# ECG_V4.net
KiCad netlist of a schematic drawn in EAGLE
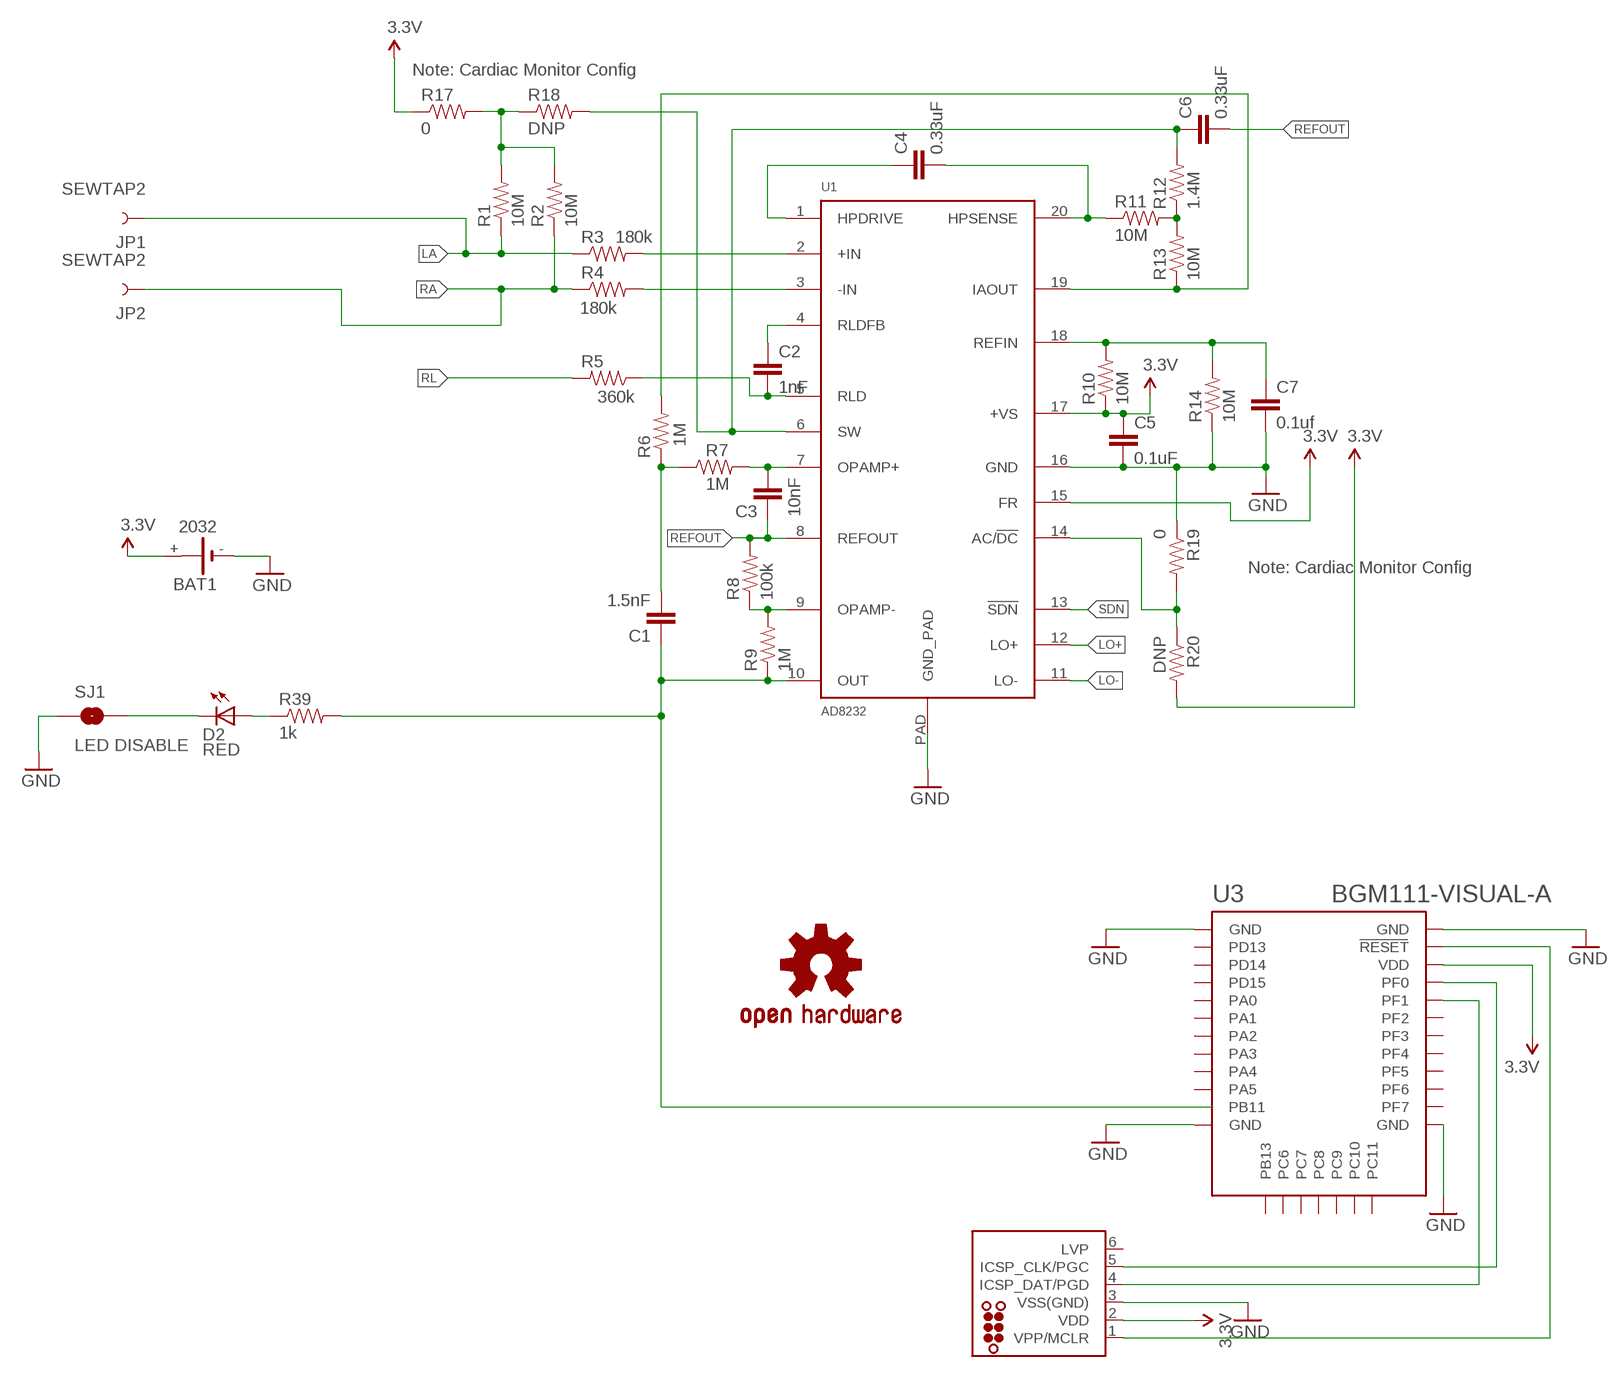
[diagram p0: schematic, sheet 1]

(export (version "E")
  (design (tool "Eeschema 10.0.6"))
  (components
    (comp (ref "BAT1")
      (value "2032")
      (footprint "eagle-import:KZH20SMD")
      (libsource (lib "eagle-import") (part "2032"))
    )
    (comp (ref "C1")
      (value "1.5nF")
      (footprint "eagle-import:0603-CAP")
      (libsource (lib "eagle-import") (part "CAP0603-CAP"))
    )
    (comp (ref "C2")
      (value "1nF")
      (footprint "eagle-import:0603-CAP")
      (libsource (lib "eagle-import") (part "CAP0603-CAP"))
    )
    (comp (ref "C3")
      (value "10nF")
      (footprint "eagle-import:0603-CAP")
      (libsource (lib "eagle-import") (part "CAP0603-CAP"))
    )
    (comp (ref "C4")
      (value "0.33uF")
      (footprint "eagle-import:0805")
      (libsource (lib "eagle-import") (part "CAP0805"))
    )
    (comp (ref "C5")
      (value "0.1uF")
      (footprint "eagle-import:0603-CAP")
      (libsource (lib "eagle-import") (part "CAP0603-CAP"))
    )
    (comp (ref "C6")
      (value "0.33uF")
      (footprint "eagle-import:0805")
      (libsource (lib "eagle-import") (part "CAP0805"))
    )
    (comp (ref "C7")
      (value "0.1uf")
      (footprint "eagle-import:0603-CAP")
      (libsource (lib "eagle-import") (part "CAP0603-CAP"))
    )
    (comp (ref "D2")
      (value "RED")
      (footprint "eagle-import:LED-0603")
      (libsource (lib "eagle-import") (part "LED-RED0603"))
    )
    (comp (ref "J2")
      (value "TC2030-MCP-NL")
      (footprint "eagle-import:TC2030-MCP-NL")
      (libsource (lib "eagle-import") (part "TC2030-MCP-NL"))
    )
    (comp (ref "JP1")
      (value "SEWTAP2")
      (footprint "eagle-import:PETAL-LONG-2")
      (libsource (lib "eagle-import") (part "SEWTAP2"))
    )
    (comp (ref "JP2")
      (value "SEWTAP2")
      (footprint "eagle-import:PETAL-LONG-2")
      (libsource (lib "eagle-import") (part "SEWTAP2"))
    )
    (comp (ref "LOGO1")
      (value "OSHW-LOGOS")
      (footprint "eagle-import:OSHW-LOGO-S")
      (libsource (lib "eagle-import") (part "OSHW-LOGOS"))
    )
    (comp (ref "R1")
      (value "10M")
      (footprint "eagle-import:0603-RES")
      (libsource (lib "eagle-import") (part "RESISTOR0603-RES"))
    )
    (comp (ref "R2")
      (value "10M")
      (footprint "eagle-import:0603-RES")
      (libsource (lib "eagle-import") (part "RESISTOR0603-RES"))
    )
    (comp (ref "R3")
      (value "180k")
      (footprint "eagle-import:0603-RES")
      (libsource (lib "eagle-import") (part "RESISTOR0603-RES"))
    )
    (comp (ref "R4")
      (value "180k")
      (footprint "eagle-import:0603-RES")
      (libsource (lib "eagle-import") (part "RESISTOR0603-RES"))
    )
    (comp (ref "R5")
      (value "360k")
      (footprint "eagle-import:0603-RES")
      (libsource (lib "eagle-import") (part "RESISTOR0603-RES"))
    )
    (comp (ref "R6")
      (value "1M")
      (footprint "eagle-import:0603-RES")
      (libsource (lib "eagle-import") (part "RESISTOR0603-RES"))
    )
    (comp (ref "R7")
      (value "1M")
      (footprint "eagle-import:0603-RES")
      (libsource (lib "eagle-import") (part "RESISTOR0603-RES"))
    )
    (comp (ref "R8")
      (value "100k")
      (footprint "eagle-import:0603-RES")
      (libsource (lib "eagle-import") (part "RESISTOR0603-RES"))
    )
    (comp (ref "R9")
      (value "1M")
      (footprint "eagle-import:0603-RES")
      (libsource (lib "eagle-import") (part "RESISTOR0603-RES"))
    )
    (comp (ref "R10")
      (value "10M")
      (footprint "eagle-import:0603-RES")
      (libsource (lib "eagle-import") (part "RESISTOR0603-RES"))
    )
    (comp (ref "R11")
      (value "10M")
      (footprint "eagle-import:0603-RES")
      (libsource (lib "eagle-import") (part "RESISTOR0603-RES"))
    )
    (comp (ref "R12")
      (value "1.4M")
      (footprint "eagle-import:0603-RES")
      (libsource (lib "eagle-import") (part "RESISTOR0603-RES"))
    )
    (comp (ref "R13")
      (value "10M")
      (footprint "eagle-import:0603-RES")
      (libsource (lib "eagle-import") (part "RESISTOR0603-RES"))
    )
    (comp (ref "R14")
      (value "10M")
      (footprint "eagle-import:0603-RES")
      (libsource (lib "eagle-import") (part "RESISTOR0603-RES"))
    )
    (comp (ref "R17")
      (value "0")
      (footprint "eagle-import:0603")
      (libsource (lib "eagle-import") (part "0OHM1/10W5%(0603)"))
    )
    (comp (ref "R18")
      (value "DNP")
      (footprint "eagle-import:0603")
      (libsource (lib "eagle-import") (part "0OHM1/10W5%(0603)"))
    )
    (comp (ref "R19")
      (value "0")
      (footprint "eagle-import:0603")
      (libsource (lib "eagle-import") (part "0OHM1/10W5%(0603)"))
    )
    (comp (ref "R20")
      (value "DNP")
      (footprint "eagle-import:0603")
      (libsource (lib "eagle-import") (part "0OHM1/10W5%(0603)"))
    )
    (comp (ref "R39")
      (value "1k")
      (footprint "eagle-import:0603-RES")
      (libsource (lib "eagle-import") (part "1K-1%"))
    )
    (comp (ref "SJ1")
      (value "LED DISABLE")
      (footprint "eagle-import:SJ_2S-TRACE")
      (libsource (lib "eagle-import") (part "SOLDERJUMPERTRACE"))
    )
    (comp (ref "U1")
      (value "AD8232")
      (footprint "eagle-import:LFCSP_20")
      (libsource (lib "eagle-import") (part "AD8232"))
    )
    (comp (ref "U3")
      (value "BGM111-VISUAL-A")
      (footprint "eagle-import:BGM111-A")
      (libsource (lib "eagle-import") (part "BGM111-VISUAL-A"))
    )
  )
  (nets
    (net (code "1") (name "3.3V") (class "Default")
      (node (ref "BAT1") (pin "+") (pinfunction "+_+") (pintype "passive"))
      (node (ref "C5") (pin "1") (pinfunction "1_1") (pintype "passive"))
      (node (ref "J2") (pin "2") (pinfunction "VDD_2") (pintype "power_in"))
      (node (ref "R10") (pin "1") (pinfunction "1_1") (pintype "passive"))
      (node (ref "R17") (pin "1") (pinfunction "1_1") (pintype "passive"))
      (node (ref "R20") (pin "2") (pinfunction "2_2") (pintype "passive"))
      (node (ref "U1") (pin "15") (pinfunction "FR_15") (pintype "bidirectional"))
      (node (ref "U1") (pin "17") (pinfunction "+VS_17") (pintype "bidirectional"))
      (node (ref "U3") (pin "VDD") (pinfunction "VDD_VDD") (pintype "power_in"))
    )
    (net (code "2") (name "GND") (class "Default")
      (node (ref "BAT1") (pin "-") (pinfunction "-_-") (pintype "passive"))
      (node (ref "C5") (pin "2") (pinfunction "2_2") (pintype "passive"))
      (node (ref "C7") (pin "2") (pinfunction "2_2") (pintype "passive"))
      (node (ref "J2") (pin "3") (pinfunction "VSS(GND)_3") (pintype "power_in"))
      (node (ref "R14") (pin "1") (pinfunction "1_1") (pintype "passive"))
      (node (ref "R19") (pin "1") (pinfunction "1_1") (pintype "passive"))
      (node (ref "SJ1") (pin "1") (pinfunction "1_1") (pintype "passive"))
      (node (ref "U1") (pin "16") (pinfunction "GND_16") (pintype "bidirectional"))
      (node (ref "U1") (pin "PAD") (pinfunction "GND_PAD_PAD") (pintype "bidirectional"))
      (node (ref "U3") (pin "GND") (pinfunction "GND_GND") (pintype "power_in"))
      (node (ref "U3") (pin "GND@2") (pinfunction "GND_GND@2") (pintype "power_in"))
      (node (ref "U3") (pin "GND@3") (pinfunction "GND_GND@3") (pintype "power_in"))
      (node (ref "U3") (pin "GND@4") (pinfunction "GND_GND@4") (pintype "power_in"))
    )
    (net (code "3") (name "LA") (class "Default")
      (node (ref "JP1") (pin "1") (pinfunction "1_1") (pintype "bidirectional"))
      (node (ref "R1") (pin "1") (pinfunction "1_1") (pintype "passive"))
      (node (ref "R3") (pin "1") (pinfunction "1_1") (pintype "passive"))
    )
    (net (code "4") (name "LO+") (class "Default")
      (node (ref "U1") (pin "12") (pinfunction "LO+_12") (pintype "bidirectional"))
    )
    (net (code "5") (name "LO-") (class "Default")
      (node (ref "U1") (pin "11") (pinfunction "LO-_11") (pintype "bidirectional"))
    )
    (net (code "6") (name "Net-(C1-Pad2)") (class "Default")
      (node (ref "C1") (pin "2") (pinfunction "2_2") (pintype "passive"))
      (node (ref "R6") (pin "1") (pinfunction "1_1") (pintype "passive"))
      (node (ref "R7") (pin "1") (pinfunction "1_1") (pintype "passive"))
    )
    (net (code "7") (name "Net-(D2-PadA)") (class "Default")
      (node (ref "D2") (pin "A") (pinfunction "A_A") (pintype "passive"))
      (node (ref "R39") (pin "1") (pinfunction "1_1") (pintype "passive"))
    )
    (net (code "8") (name "Net-(D2-PadC)") (class "Default")
      (node (ref "D2") (pin "C") (pinfunction "C_C") (pintype "passive"))
      (node (ref "SJ1") (pin "2") (pinfunction "2_2") (pintype "passive"))
    )
    (net (code "9") (name "Net-(J2-ICSP_CLK{slash}PGC)") (class "Default")
      (node (ref "J2") (pin "5") (pinfunction "ICSP_CLK/PGC_5") (pintype "output"))
      (node (ref "U3") (pin "PF0") (pinfunction "PF0_PF0") (pintype "bidirectional"))
    )
    (net (code "10") (name "Net-(J2-ICSP_DAT{slash}PGD)") (class "Default")
      (node (ref "J2") (pin "4") (pinfunction "ICSP_DAT/PGD_4") (pintype "bidirectional"))
      (node (ref "U3") (pin "PF1") (pinfunction "PF1_PF1") (pintype "bidirectional"))
    )
    (net (code "11") (name "Net-(J2-VPP{slash}MCLR)") (class "Default")
      (node (ref "J2") (pin "1") (pinfunction "VPP/MCLR_1") (pintype "passive"))
      (node (ref "U3") (pin "RESET") (pinfunction "RESET_RESET") (pintype "input"))
    )
    (net (code "12") (name "Net-(R1-Pad2)") (class "Default")
      (node (ref "R1") (pin "2") (pinfunction "2_2") (pintype "passive"))
      (node (ref "R17") (pin "2") (pinfunction "2_2") (pintype "passive"))
      (node (ref "R18") (pin "1") (pinfunction "1_1") (pintype "passive"))
      (node (ref "R2") (pin "2") (pinfunction "2_2") (pintype "passive"))
    )
    (net (code "13") (name "Net-(R11-Pad2)") (class "Default")
      (node (ref "R11") (pin "2") (pinfunction "2_2") (pintype "passive"))
      (node (ref "R12") (pin "1") (pinfunction "1_1") (pintype "passive"))
      (node (ref "R13") (pin "2") (pinfunction "2_2") (pintype "passive"))
    )
    (net (code "14") (name "Net-(U1-+IN)") (class "Default")
      (node (ref "R3") (pin "2") (pinfunction "2_2") (pintype "passive"))
      (node (ref "U1") (pin "2") (pinfunction "+IN_2") (pintype "bidirectional"))
    )
    (net (code "15") (name "Net-(U1--IN)") (class "Default")
      (node (ref "R4") (pin "2") (pinfunction "2_2") (pintype "passive"))
      (node (ref "U1") (pin "3") (pinfunction "-IN_3") (pintype "bidirectional"))
    )
    (net (code "16") (name "Net-(U1-AC{slash}~{DC})") (class "Default")
      (node (ref "R19") (pin "2") (pinfunction "2_2") (pintype "passive"))
      (node (ref "R20") (pin "1") (pinfunction "1_1") (pintype "passive"))
      (node (ref "U1") (pin "14") (pinfunction "AC/~{DC}_14") (pintype "bidirectional"))
    )
    (net (code "17") (name "Net-(U1-HPDRIVE)") (class "Default")
      (node (ref "C4") (pin "1") (pinfunction "1_1") (pintype "passive"))
      (node (ref "U1") (pin "1") (pinfunction "HPDRIVE_1") (pintype "bidirectional"))
    )
    (net (code "18") (name "Net-(U1-HPSENSE)") (class "Default")
      (node (ref "C4") (pin "2") (pinfunction "2_2") (pintype "passive"))
      (node (ref "R11") (pin "1") (pinfunction "1_1") (pintype "passive"))
      (node (ref "U1") (pin "20") (pinfunction "HPSENSE_20") (pintype "bidirectional"))
    )
    (net (code "19") (name "Net-(U1-IAOUT)") (class "Default")
      (node (ref "R13") (pin "1") (pinfunction "1_1") (pintype "passive"))
      (node (ref "R6") (pin "2") (pinfunction "2_2") (pintype "passive"))
      (node (ref "U1") (pin "19") (pinfunction "IAOUT_19") (pintype "bidirectional"))
    )
    (net (code "20") (name "Net-(U1-OPAMP+)") (class "Default")
      (node (ref "C3") (pin "2") (pinfunction "2_2") (pintype "passive"))
      (node (ref "R7") (pin "2") (pinfunction "2_2") (pintype "passive"))
      (node (ref "U1") (pin "7") (pinfunction "OPAMP+_7") (pintype "bidirectional"))
    )
    (net (code "21") (name "Net-(U1-OPAMP-)") (class "Default")
      (node (ref "R8") (pin "1") (pinfunction "1_1") (pintype "passive"))
      (node (ref "R9") (pin "2") (pinfunction "2_2") (pintype "passive"))
      (node (ref "U1") (pin "9") (pinfunction "OPAMP-_9") (pintype "bidirectional"))
    )
    (net (code "22") (name "Net-(U1-OUT)") (class "Default")
      (node (ref "C1") (pin "1") (pinfunction "1_1") (pintype "passive"))
      (node (ref "R39") (pin "2") (pinfunction "2_2") (pintype "passive"))
      (node (ref "R9") (pin "1") (pinfunction "1_1") (pintype "passive"))
      (node (ref "U1") (pin "10") (pinfunction "OUT_10") (pintype "bidirectional"))
    )
    (net (code "23") (name "Net-(U1-REFIN)") (class "Default")
      (node (ref "C7") (pin "1") (pinfunction "1_1") (pintype "passive"))
      (node (ref "R10") (pin "2") (pinfunction "2_2") (pintype "passive"))
      (node (ref "R14") (pin "2") (pinfunction "2_2") (pintype "passive"))
      (node (ref "U1") (pin "18") (pinfunction "REFIN_18") (pintype "bidirectional"))
    )
    (net (code "24") (name "Net-(U1-RLD)") (class "Default")
      (node (ref "C2") (pin "2") (pinfunction "2_2") (pintype "passive"))
      (node (ref "R5") (pin "1") (pinfunction "1_1") (pintype "passive"))
      (node (ref "U1") (pin "5") (pinfunction "RLD_5") (pintype "bidirectional"))
    )
    (net (code "25") (name "Net-(U1-RLDFB)") (class "Default")
      (node (ref "C2") (pin "1") (pinfunction "1_1") (pintype "passive"))
      (node (ref "U1") (pin "4") (pinfunction "RLDFB_4") (pintype "bidirectional"))
    )
    (net (code "26") (name "Net-(U1-SW)") (class "Default")
      (node (ref "C6") (pin "1") (pinfunction "1_1") (pintype "passive"))
      (node (ref "R12") (pin "2") (pinfunction "2_2") (pintype "passive"))
      (node (ref "R18") (pin "2") (pinfunction "2_2") (pintype "passive"))
      (node (ref "U1") (pin "6") (pinfunction "SW_6") (pintype "bidirectional"))
    )
    (net (code "27") (name "RA") (class "Default")
      (node (ref "JP2") (pin "1") (pinfunction "1_1") (pintype "bidirectional"))
      (node (ref "R2") (pin "1") (pinfunction "1_1") (pintype "passive"))
      (node (ref "R4") (pin "1") (pinfunction "1_1") (pintype "passive"))
    )
    (net (code "28") (name "REFOUT") (class "Default")
      (node (ref "C3") (pin "1") (pinfunction "1_1") (pintype "passive"))
      (node (ref "C6") (pin "2") (pinfunction "2_2") (pintype "passive"))
      (node (ref "R8") (pin "2") (pinfunction "2_2") (pintype "passive"))
      (node (ref "U1") (pin "8") (pinfunction "REFOUT_8") (pintype "bidirectional"))
    )
    (net (code "29") (name "RL") (class "Default")
      (node (ref "R5") (pin "2") (pinfunction "2_2") (pintype "passive"))
    )
    (net (code "30") (name "SDN") (class "Default")
      (node (ref "U1") (pin "13") (pinfunction "~{SDN}_13") (pintype "bidirectional"))
    )
    (net (code "31") (name "unconnected-(J2-LVP-Pad6)") (class "Default")
      (node (ref "J2") (pin "6") (pinfunction "LVP_6") (pintype "bidirectional"))
    )
    (net (code "32") (name "unconnected-(U3-PadPA0)") (class "Default")
      (node (ref "U3") (pin "PA0") (pinfunction "PA0_PA0") (pintype "bidirectional"))
    )
    (net (code "33") (name "unconnected-(U3-PadPA1)") (class "Default")
      (node (ref "U3") (pin "PA1") (pinfunction "PA1_PA1") (pintype "bidirectional"))
    )
    (net (code "34") (name "unconnected-(U3-PadPA2)") (class "Default")
      (node (ref "U3") (pin "PA2") (pinfunction "PA2_PA2") (pintype "bidirectional"))
    )
    (net (code "35") (name "unconnected-(U3-PadPA3)") (class "Default")
      (node (ref "U3") (pin "PA3") (pinfunction "PA3_PA3") (pintype "bidirectional"))
    )
    (net (code "36") (name "unconnected-(U3-PadPA4)") (class "Default")
      (node (ref "U3") (pin "PA4") (pinfunction "PA4_PA4") (pintype "bidirectional"))
    )
    (net (code "37") (name "unconnected-(U3-PadPA5)") (class "Default")
      (node (ref "U3") (pin "PA5") (pinfunction "PA5_PA5") (pintype "bidirectional"))
    )
    (net (code "38") (name "unconnected-(U3-PadPB11)") (class "Default")
      (node (ref "U3") (pin "PB11") (pinfunction "PB11_PB11") (pintype "bidirectional"))
    )
    (net (code "39") (name "unconnected-(U3-PadPB13)") (class "Default")
      (node (ref "U3") (pin "PB13") (pinfunction "PB13_PB13") (pintype "bidirectional"))
    )
    (net (code "40") (name "unconnected-(U3-PadPC6)") (class "Default")
      (node (ref "U3") (pin "PC6") (pinfunction "PC6_PC6") (pintype "bidirectional"))
    )
    (net (code "41") (name "unconnected-(U3-PadPC7)") (class "Default")
      (node (ref "U3") (pin "PC7") (pinfunction "PC7_PC7") (pintype "bidirectional"))
    )
    (net (code "42") (name "unconnected-(U3-PadPC8)") (class "Default")
      (node (ref "U3") (pin "PC8") (pinfunction "PC8_PC8") (pintype "bidirectional"))
    )
    (net (code "43") (name "unconnected-(U3-PadPC9)") (class "Default")
      (node (ref "U3") (pin "PC9") (pinfunction "PC9_PC9") (pintype "bidirectional"))
    )
    (net (code "44") (name "unconnected-(U3-PadPC10)") (class "Default")
      (node (ref "U3") (pin "PC10") (pinfunction "PC10_PC10") (pintype "bidirectional"))
    )
    (net (code "45") (name "unconnected-(U3-PadPC11)") (class "Default")
      (node (ref "U3") (pin "PC11") (pinfunction "PC11_PC11") (pintype "bidirectional"))
    )
    (net (code "46") (name "unconnected-(U3-PadPD13)") (class "Default")
      (node (ref "U3") (pin "PD13") (pinfunction "PD13_PD13") (pintype "bidirectional"))
    )
    (net (code "47") (name "unconnected-(U3-PadPD14)") (class "Default")
      (node (ref "U3") (pin "PD14") (pinfunction "PD14_PD14") (pintype "bidirectional"))
    )
    (net (code "48") (name "unconnected-(U3-PadPD15)") (class "Default")
      (node (ref "U3") (pin "PD15") (pinfunction "PD15_PD15") (pintype "bidirectional"))
    )
    (net (code "49") (name "unconnected-(U3-PadPF2)") (class "Default")
      (node (ref "U3") (pin "PF2") (pinfunction "PF2_PF2") (pintype "bidirectional"))
    )
    (net (code "50") (name "unconnected-(U3-PadPF3)") (class "Default")
      (node (ref "U3") (pin "PF3") (pinfunction "PF3_PF3") (pintype "bidirectional"))
    )
    (net (code "51") (name "unconnected-(U3-PadPF4)") (class "Default")
      (node (ref "U3") (pin "PF4") (pinfunction "PF4_PF4") (pintype "bidirectional"))
    )
    (net (code "52") (name "unconnected-(U3-PadPF5)") (class "Default")
      (node (ref "U3") (pin "PF5") (pinfunction "PF5_PF5") (pintype "bidirectional"))
    )
    (net (code "53") (name "unconnected-(U3-PadPF6)") (class "Default")
      (node (ref "U3") (pin "PF6") (pinfunction "PF6_PF6") (pintype "bidirectional"))
    )
    (net (code "54") (name "unconnected-(U3-PadPF7)") (class "Default")
      (node (ref "U3") (pin "PF7") (pinfunction "PF7_PF7") (pintype "bidirectional"))
    )
  )
)
